# remoticon.net
KiCad netlist of a schematic drawn in EAGLE
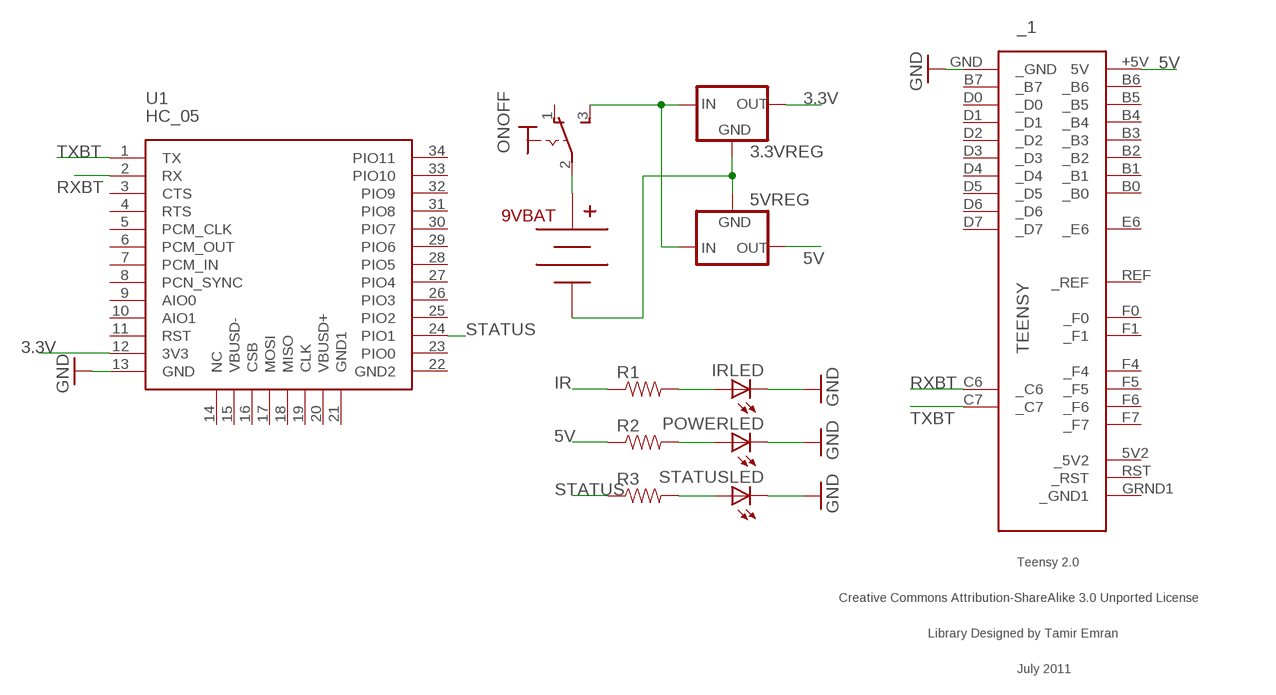
[diagram p0: schematic, sheet 1]

(export (version "E")
  (design (tool "Eeschema 10.0.6"))
  (components
    (comp (ref "3.3VREG")
      (value "V_REG_LD1117VXX")
      (footprint "eagle-import:78XXL")
      (libsource (lib "eagle-import") (part "V_REG_LD1117VXX"))
    )
    (comp (ref "5VREG")
      (value "V_REG_78XX-TO-220")
      (footprint "eagle-import:TO-220-ALT")
      (libsource (lib "eagle-import") (part "V_REG_78XX-TO-220"))
    )
    (comp (ref "9VBAT")
      (value "BC9VPC")
      (footprint "eagle-import:BC9VPC")
      (libsource (lib "eagle-import") (part "BC9VPC"))
    )
    (comp (ref "IRLED")
      (value "LED5MM")
      (footprint "eagle-import:LED5MM")
      (libsource (lib "eagle-import") (part "LED5MM"))
    )
    (comp (ref "ONOFF")
      (value "320-916")
      (footprint "eagle-import:320-916")
      (libsource (lib "eagle-import") (part "320-916"))
    )
    (comp (ref "POWERLED")
      (value "LED5MM")
      (footprint "eagle-import:LED5MM")
      (libsource (lib "eagle-import") (part "LED5MM"))
    )
    (comp (ref "R1")
      (value "RESISTOREZ")
      (footprint "eagle-import:AXIAL-0.3EZ")
      (libsource (lib "eagle-import") (part "RESISTOREZ"))
    )
    (comp (ref "R2")
      (value "RESISTOREZ")
      (footprint "eagle-import:AXIAL-0.3EZ")
      (libsource (lib "eagle-import") (part "RESISTOREZ"))
    )
    (comp (ref "R3")
      (value "RESISTOREZ")
      (footprint "eagle-import:AXIAL-0.3EZ")
      (libsource (lib "eagle-import") (part "RESISTOREZ"))
    )
    (comp (ref "STATUSLED")
      (value "LED5MM")
      (footprint "eagle-import:LED5MM")
      (libsource (lib "eagle-import") (part "LED5MM"))
    )
    (comp (ref "U1")
      (value "HC_05")
      (footprint "eagle-import:BLUETOOTH_SMD")
      (libsource (lib "eagle-import") (part "HC_05"))
    )
    (comp (ref "_1")
      (value "TEENSY")
      (footprint "eagle-import:TEENSY")
      (libsource (lib "eagle-import") (part "TEENSY"))
    )
  )
  (nets
    (net (code "1") (name "/3.3V") (class "Default")
      (node (ref "3.3VREG") (pin "GND") (pinfunction "OUT_GND") (pintype "output"))
      (node (ref "U1") (pin "12") (pinfunction "3V3_12") (pintype "bidirectional"))
    )
    (net (code "2") (name "/5V") (class "Default")
      (node (ref "5VREG") (pin "OUT") (pinfunction "OUT_OUT") (pintype "output"))
      (node (ref "R2") (pin "P$1") (pinfunction "1_P$1") (pintype "passive"))
      (node (ref "_1") (pin "+5V") (pinfunction "5V_+5V") (pintype "bidirectional"))
    )
    (net (code "3") (name "/IR") (class "Default")
      (node (ref "R1") (pin "P$1") (pinfunction "1_P$1") (pintype "passive"))
    )
    (net (code "4") (name "/RXBT") (class "Default")
      (node (ref "U1") (pin "2") (pinfunction "RX_2") (pintype "bidirectional"))
      (node (ref "_1") (pin "C6") (pinfunction "_C6_C6") (pintype "bidirectional"))
    )
    (net (code "5") (name "/STATUS") (class "Default")
      (node (ref "R3") (pin "P$1") (pinfunction "1_P$1") (pintype "passive"))
      (node (ref "U1") (pin "24") (pinfunction "PIO1_24") (pintype "bidirectional"))
    )
    (net (code "6") (name "/TXBT") (class "Default")
      (node (ref "U1") (pin "1") (pinfunction "TX_1") (pintype "bidirectional"))
      (node (ref "_1") (pin "C7") (pinfunction "_C7_C7") (pintype "bidirectional"))
    )
    (net (code "7") (name "GND") (class "Default")
      (node (ref "IRLED") (pin "K") (pinfunction "C_K") (pintype "passive"))
      (node (ref "POWERLED") (pin "K") (pinfunction "C_K") (pintype "passive"))
      (node (ref "STATUSLED") (pin "K") (pinfunction "C_K") (pintype "passive"))
      (node (ref "U1") (pin "13") (pinfunction "GND_13") (pintype "bidirectional"))
      (node (ref "_1") (pin "GND") (pinfunction "_GND_GND") (pintype "bidirectional"))
    )
    (net (code "8") (name "Net-(3.3VREG-GND)") (class "Default")
      (node (ref "3.3VREG") (pin "IN") (pinfunction "GND_IN") (pintype "input"))
      (node (ref "5VREG") (pin "GND") (pinfunction "GND_GND") (pintype "input"))
      (node (ref "9VBAT") (pin "V-") (pinfunction "V-_V-") (pintype "bidirectional"))
    )
    (net (code "9") (name "Net-(3.3VREG-IN)") (class "Default")
      (node (ref "3.3VREG") (pin "OUT") (pinfunction "IN_OUT") (pintype "input"))
      (node (ref "5VREG") (pin "IN") (pinfunction "IN_IN") (pintype "input"))
      (node (ref "ONOFF") (pin "3") (pinfunction "S_3") (pintype "passive"))
    )
    (net (code "10") (name "Net-(ONOFF-P)") (class "Default")
      (node (ref "9VBAT") (pin "V+") (pinfunction "V+_V+") (pintype "bidirectional"))
      (node (ref "ONOFF") (pin "2") (pinfunction "P_2") (pintype "passive"))
    )
    (net (code "11") (name "Net-(R1-2)") (class "Default")
      (node (ref "IRLED") (pin "A") (pinfunction "A_A") (pintype "passive"))
      (node (ref "R1") (pin "P$2") (pinfunction "2_P$2") (pintype "passive"))
    )
    (net (code "12") (name "Net-(R2-2)") (class "Default")
      (node (ref "POWERLED") (pin "A") (pinfunction "A_A") (pintype "passive"))
      (node (ref "R2") (pin "P$2") (pinfunction "2_P$2") (pintype "passive"))
    )
    (net (code "13") (name "Net-(R3-2)") (class "Default")
      (node (ref "R3") (pin "P$2") (pinfunction "2_P$2") (pintype "passive"))
      (node (ref "STATUSLED") (pin "A") (pinfunction "A_A") (pintype "passive"))
    )
    (net (code "14") (name "unconnected-(ONOFF-O-Pad1)") (class "Default")
      (node (ref "ONOFF") (pin "1") (pinfunction "O_1") (pintype "passive"))
    )
    (net (code "15") (name "unconnected-(U1-AIO0-Pad9)") (class "Default")
      (node (ref "U1") (pin "9") (pinfunction "AIO0_9") (pintype "bidirectional"))
    )
    (net (code "16") (name "unconnected-(U1-AIO1-Pad10)") (class "Default")
      (node (ref "U1") (pin "10") (pinfunction "AIO1_10") (pintype "bidirectional"))
    )
    (net (code "17") (name "unconnected-(U1-CLK-Pad19)") (class "Default")
      (node (ref "U1") (pin "19") (pinfunction "CLK_19") (pintype "bidirectional"))
    )
    (net (code "18") (name "unconnected-(U1-CSB-Pad16)") (class "Default")
      (node (ref "U1") (pin "16") (pinfunction "CSB_16") (pintype "bidirectional"))
    )
    (net (code "19") (name "unconnected-(U1-CTS-Pad3)") (class "Default")
      (node (ref "U1") (pin "3") (pinfunction "CTS_3") (pintype "bidirectional"))
    )
    (net (code "20") (name "unconnected-(U1-GND1-Pad21)") (class "Default")
      (node (ref "U1") (pin "21") (pinfunction "GND1_21") (pintype "bidirectional"))
    )
    (net (code "21") (name "unconnected-(U1-GND2-Pad22)") (class "Default")
      (node (ref "U1") (pin "22") (pinfunction "GND2_22") (pintype "bidirectional"))
    )
    (net (code "22") (name "unconnected-(U1-MISO-Pad18)") (class "Default")
      (node (ref "U1") (pin "18") (pinfunction "MISO_18") (pintype "bidirectional"))
    )
    (net (code "23") (name "unconnected-(U1-MOSI-Pad17)") (class "Default")
      (node (ref "U1") (pin "17") (pinfunction "MOSI_17") (pintype "bidirectional"))
    )
    (net (code "24") (name "unconnected-(U1-NC-Pad14)") (class "Default")
      (node (ref "U1") (pin "14") (pinfunction "NC_14") (pintype "bidirectional"))
    )
    (net (code "25") (name "unconnected-(U1-PCM_CLK-Pad5)") (class "Default")
      (node (ref "U1") (pin "5") (pinfunction "PCM_CLK_5") (pintype "bidirectional"))
    )
    (net (code "26") (name "unconnected-(U1-PCM_IN-Pad7)") (class "Default")
      (node (ref "U1") (pin "7") (pinfunction "PCM_IN_7") (pintype "bidirectional"))
    )
    (net (code "27") (name "unconnected-(U1-PCM_OUT-Pad6)") (class "Default")
      (node (ref "U1") (pin "6") (pinfunction "PCM_OUT_6") (pintype "bidirectional"))
    )
    (net (code "28") (name "unconnected-(U1-PCN_SYNC-Pad8)") (class "Default")
      (node (ref "U1") (pin "8") (pinfunction "PCN_SYNC_8") (pintype "bidirectional"))
    )
    (net (code "29") (name "unconnected-(U1-PIO0-Pad23)") (class "Default")
      (node (ref "U1") (pin "23") (pinfunction "PIO0_23") (pintype "bidirectional"))
    )
    (net (code "30") (name "unconnected-(U1-PIO2-Pad25)") (class "Default")
      (node (ref "U1") (pin "25") (pinfunction "PIO2_25") (pintype "bidirectional"))
    )
    (net (code "31") (name "unconnected-(U1-PIO3-Pad26)") (class "Default")
      (node (ref "U1") (pin "26") (pinfunction "PIO3_26") (pintype "bidirectional"))
    )
    (net (code "32") (name "unconnected-(U1-PIO4-Pad27)") (class "Default")
      (node (ref "U1") (pin "27") (pinfunction "PIO4_27") (pintype "bidirectional"))
    )
    (net (code "33") (name "unconnected-(U1-PIO5-Pad28)") (class "Default")
      (node (ref "U1") (pin "28") (pinfunction "PIO5_28") (pintype "bidirectional"))
    )
    (net (code "34") (name "unconnected-(U1-PIO6-Pad29)") (class "Default")
      (node (ref "U1") (pin "29") (pinfunction "PIO6_29") (pintype "bidirectional"))
    )
    (net (code "35") (name "unconnected-(U1-PIO7-Pad30)") (class "Default")
      (node (ref "U1") (pin "30") (pinfunction "PIO7_30") (pintype "bidirectional"))
    )
    (net (code "36") (name "unconnected-(U1-PIO8-Pad31)") (class "Default")
      (node (ref "U1") (pin "31") (pinfunction "PIO8_31") (pintype "bidirectional"))
    )
    (net (code "37") (name "unconnected-(U1-PIO9-Pad32)") (class "Default")
      (node (ref "U1") (pin "32") (pinfunction "PIO9_32") (pintype "bidirectional"))
    )
    (net (code "38") (name "unconnected-(U1-PIO10-Pad33)") (class "Default")
      (node (ref "U1") (pin "33") (pinfunction "PIO10_33") (pintype "bidirectional"))
    )
    (net (code "39") (name "unconnected-(U1-PIO11-Pad34)") (class "Default")
      (node (ref "U1") (pin "34") (pinfunction "PIO11_34") (pintype "bidirectional"))
    )
    (net (code "40") (name "unconnected-(U1-RST-Pad11)") (class "Default")
      (node (ref "U1") (pin "11") (pinfunction "RST_11") (pintype "bidirectional"))
    )
    (net (code "41") (name "unconnected-(U1-RTS-Pad4)") (class "Default")
      (node (ref "U1") (pin "4") (pinfunction "RTS_4") (pintype "bidirectional"))
    )
    (net (code "42") (name "unconnected-(U1-VBUSD+-Pad20)") (class "Default")
      (node (ref "U1") (pin "20") (pinfunction "VBUSD+_20") (pintype "bidirectional"))
    )
    (net (code "43") (name "unconnected-(U1-VBUSD--Pad15)") (class "Default")
      (node (ref "U1") (pin "15") (pinfunction "VBUSD-_15") (pintype "bidirectional"))
    )
    (net (code "44") (name "unconnected-(_1-_5V2-Pad5V2)") (class "Default")
      (node (ref "_1") (pin "5V2") (pinfunction "_5V2_5V2") (pintype "bidirectional"))
    )
    (net (code "45") (name "unconnected-(_1-_B0-PadB0)") (class "Default")
      (node (ref "_1") (pin "B0") (pinfunction "_B0_B0") (pintype "bidirectional"))
    )
    (net (code "46") (name "unconnected-(_1-_B1-PadB1)") (class "Default")
      (node (ref "_1") (pin "B1") (pinfunction "_B1_B1") (pintype "bidirectional"))
    )
    (net (code "47") (name "unconnected-(_1-_B2-PadB2)") (class "Default")
      (node (ref "_1") (pin "B2") (pinfunction "_B2_B2") (pintype "bidirectional"))
    )
    (net (code "48") (name "unconnected-(_1-_B3-PadB3)") (class "Default")
      (node (ref "_1") (pin "B3") (pinfunction "_B3_B3") (pintype "bidirectional"))
    )
    (net (code "49") (name "unconnected-(_1-_B4-PadB4)") (class "Default")
      (node (ref "_1") (pin "B4") (pinfunction "_B4_B4") (pintype "bidirectional"))
    )
    (net (code "50") (name "unconnected-(_1-_B5-PadB5)") (class "Default")
      (node (ref "_1") (pin "B5") (pinfunction "_B5_B5") (pintype "bidirectional"))
    )
    (net (code "51") (name "unconnected-(_1-_B6-PadB6)") (class "Default")
      (node (ref "_1") (pin "B6") (pinfunction "_B6_B6") (pintype "bidirectional"))
    )
    (net (code "52") (name "unconnected-(_1-_B7-PadB7)") (class "Default")
      (node (ref "_1") (pin "B7") (pinfunction "_B7_B7") (pintype "bidirectional"))
    )
    (net (code "53") (name "unconnected-(_1-_D0-PadD0)") (class "Default")
      (node (ref "_1") (pin "D0") (pinfunction "_D0_D0") (pintype "bidirectional"))
    )
    (net (code "54") (name "unconnected-(_1-_D1-PadD1)") (class "Default")
      (node (ref "_1") (pin "D1") (pinfunction "_D1_D1") (pintype "bidirectional"))
    )
    (net (code "55") (name "unconnected-(_1-_D2-PadD2)") (class "Default")
      (node (ref "_1") (pin "D2") (pinfunction "_D2_D2") (pintype "bidirectional"))
    )
    (net (code "56") (name "unconnected-(_1-_D3-PadD3)") (class "Default")
      (node (ref "_1") (pin "D3") (pinfunction "_D3_D3") (pintype "bidirectional"))
    )
    (net (code "57") (name "unconnected-(_1-_D4-PadD4)") (class "Default")
      (node (ref "_1") (pin "D4") (pinfunction "_D4_D4") (pintype "bidirectional"))
    )
    (net (code "58") (name "unconnected-(_1-_D5-PadD5)") (class "Default")
      (node (ref "_1") (pin "D5") (pinfunction "_D5_D5") (pintype "bidirectional"))
    )
    (net (code "59") (name "unconnected-(_1-_D6-PadD6)") (class "Default")
      (node (ref "_1") (pin "D6") (pinfunction "_D6_D6") (pintype "bidirectional"))
    )
    (net (code "60") (name "unconnected-(_1-_D7-PadD7)") (class "Default")
      (node (ref "_1") (pin "D7") (pinfunction "_D7_D7") (pintype "bidirectional"))
    )
    (net (code "61") (name "unconnected-(_1-_E6-PadE6)") (class "Default")
      (node (ref "_1") (pin "E6") (pinfunction "_E6_E6") (pintype "bidirectional"))
    )
    (net (code "62") (name "unconnected-(_1-_F0-PadF0)") (class "Default")
      (node (ref "_1") (pin "F0") (pinfunction "_F0_F0") (pintype "bidirectional"))
    )
    (net (code "63") (name "unconnected-(_1-_F1-PadF1)") (class "Default")
      (node (ref "_1") (pin "F1") (pinfunction "_F1_F1") (pintype "bidirectional"))
    )
    (net (code "64") (name "unconnected-(_1-_F4-PadF4)") (class "Default")
      (node (ref "_1") (pin "F4") (pinfunction "_F4_F4") (pintype "bidirectional"))
    )
    (net (code "65") (name "unconnected-(_1-_F5-PadF5)") (class "Default")
      (node (ref "_1") (pin "F5") (pinfunction "_F5_F5") (pintype "bidirectional"))
    )
    (net (code "66") (name "unconnected-(_1-_F6-PadF6)") (class "Default")
      (node (ref "_1") (pin "F6") (pinfunction "_F6_F6") (pintype "bidirectional"))
    )
    (net (code "67") (name "unconnected-(_1-_F7-PadF7)") (class "Default")
      (node (ref "_1") (pin "F7") (pinfunction "_F7_F7") (pintype "bidirectional"))
    )
    (net (code "68") (name "unconnected-(_1-_GND1-PadGRND1)") (class "Default")
      (node (ref "_1") (pin "GRND1") (pinfunction "_GND1_GRND1") (pintype "bidirectional"))
    )
    (net (code "69") (name "unconnected-(_1-_REF-PadREF)") (class "Default")
      (node (ref "_1") (pin "REF") (pinfunction "_REF_REF") (pintype "bidirectional"))
    )
    (net (code "70") (name "unconnected-(_1-_RST-PadRST)") (class "Default")
      (node (ref "_1") (pin "RST") (pinfunction "_RST_RST") (pintype "bidirectional"))
    )
  )
)
